# Z80Console0000.net
KiCad netlist of a schematic drawn in Altium Designer
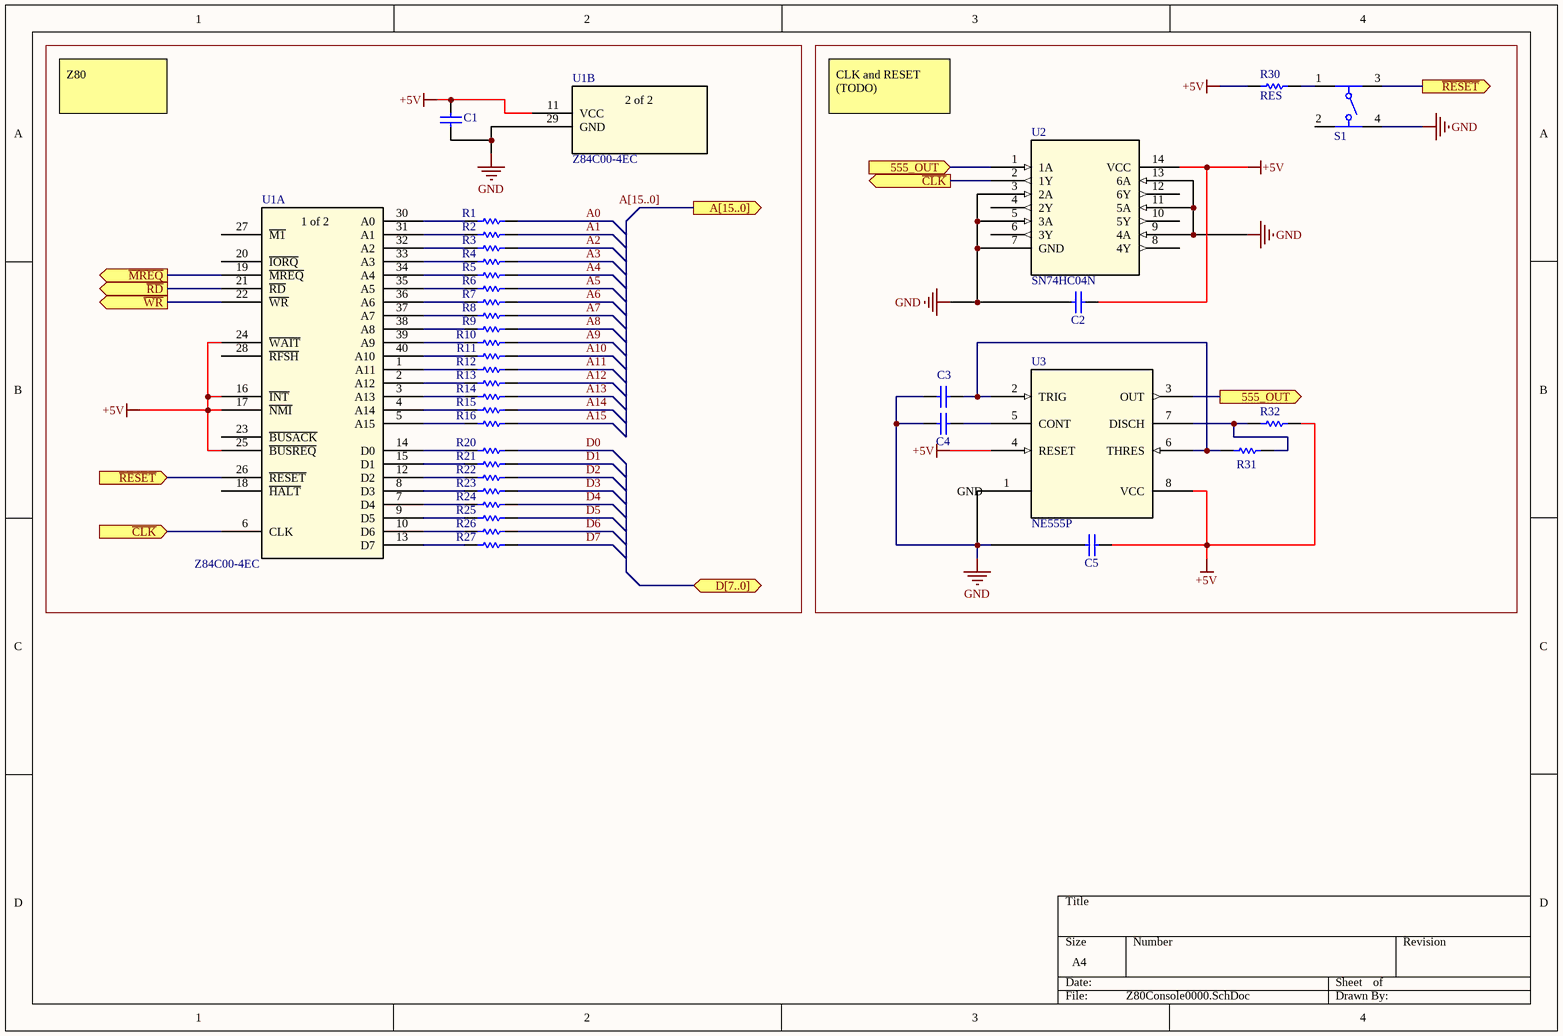
[diagram p0: Z80Console0000.SchDoc]

(export (version "E")
  (design (tool "Eeschema 10.0.6"))
  (components
    (comp (ref "C1")
      (value "CAP")
      (footprint "CAPC0603(1608)100_N")
      (libsource (lib "Passive SMD") (part "CAP"))
    )
    (comp (ref "C2")
      (value "CAP")
      (footprint "CAPC0603(1608)100_N")
      (libsource (lib "Passive SMD") (part "CAP"))
    )
    (comp (ref "C3")
      (value "CAP")
      (footprint "CAPC0603(1608)100_N")
      (libsource (lib "Passive SMD") (part "CAP"))
    )
    (comp (ref "C4")
      (value "CAP")
      (footprint "CAPC0603(1608)100_N")
      (libsource (lib "Passive SMD") (part "CAP"))
    )
    (comp (ref "C5")
      (value "CAP")
      (footprint "CAPC0603(1608)100_N")
      (libsource (lib "Passive SMD") (part "CAP"))
    )
    (comp (ref "R1") (value "RES") (footprint "RES_2512_MELF") (libsource (lib "Passive SMD") (part "RES")))
    (comp (ref "R2") (value "RES") (footprint "RES_2512_MELF") (libsource (lib "Passive SMD") (part "RES")))
    (comp (ref "R3") (value "RES") (footprint "RES_2512_MELF") (libsource (lib "Passive SMD") (part "RES")))
    (comp (ref "R4") (value "RES") (footprint "RES_2512_MELF") (libsource (lib "Passive SMD") (part "RES")))
    (comp (ref "R5") (value "RES") (footprint "RES_2512_MELF") (libsource (lib "Passive SMD") (part "RES")))
    (comp (ref "R6") (value "RES") (footprint "RES_2512_MELF") (libsource (lib "Passive SMD") (part "RES")))
    (comp (ref "R7") (value "RES") (footprint "RES_2512_MELF") (libsource (lib "Passive SMD") (part "RES")))
    (comp (ref "R8") (value "RES") (footprint "RES_2512_MELF") (libsource (lib "Passive SMD") (part "RES")))
    (comp (ref "R9") (value "RES") (footprint "RES_2512_MELF") (libsource (lib "Passive SMD") (part "RES")))
    (comp (ref "R10") (value "RES") (footprint "RES_2512_MELF") (libsource (lib "Passive SMD") (part "RES")))
    (comp (ref "R11") (value "RES") (footprint "RES_2512_MELF") (libsource (lib "Passive SMD") (part "RES")))
    (comp (ref "R12") (value "RES") (footprint "RES_2512_MELF") (libsource (lib "Passive SMD") (part "RES")))
    (comp (ref "R13") (value "RES") (footprint "RES_2512_MELF") (libsource (lib "Passive SMD") (part "RES")))
    (comp (ref "R14") (value "RES") (footprint "RES_2512_MELF") (libsource (lib "Passive SMD") (part "RES")))
    (comp (ref "R15") (value "RES") (footprint "RES_2512_MELF") (libsource (lib "Passive SMD") (part "RES")))
    (comp (ref "R16") (value "RES") (footprint "RES_2512_MELF") (libsource (lib "Passive SMD") (part "RES")))
    (comp (ref "R20") (value "RES") (footprint "RES_2512_MELF") (libsource (lib "Passive SMD") (part "RES")))
    (comp (ref "R21") (value "RES") (footprint "RES_2512_MELF") (libsource (lib "Passive SMD") (part "RES")))
    (comp (ref "R22") (value "RES") (footprint "RES_2512_MELF") (libsource (lib "Passive SMD") (part "RES")))
    (comp (ref "R23") (value "RES") (footprint "RES_2512_MELF") (libsource (lib "Passive SMD") (part "RES")))
    (comp (ref "R24") (value "RES") (footprint "RES_2512_MELF") (libsource (lib "Passive SMD") (part "RES")))
    (comp (ref "R25") (value "RES") (footprint "RES_2512_MELF") (libsource (lib "Passive SMD") (part "RES")))
    (comp (ref "R26") (value "RES") (footprint "RES_2512_MELF") (libsource (lib "Passive SMD") (part "RES")))
    (comp (ref "R27") (value "RES") (footprint "RES_2512_MELF") (libsource (lib "Passive SMD") (part "RES")))
    (comp (ref "R30") (value "RES") (footprint "RES_2512_MELF") (libsource (lib "Passive SMD") (part "RES")))
    (comp (ref "R31") (value "RES") (footprint "RES_2512_MELF") (libsource (lib "Passive SMD") (part "RES")))
    (comp (ref "R32") (value "RES") (footprint "RES_2512_MELF") (libsource (lib "Passive SMD") (part "RES")))
    (comp (ref "S1")
      (value "430156043726")
      (footprint "4301x60437x6_6x6x4.3")
      (description "WS-TATV 6x6mm Tact Switch, THT version")
      (fields (field (name "PUBLISHER") "Wurth Elektronik"))
      (libsource (lib "Wurth_WS-TATV-rev17a") (part "430156043726"))
    )
    (comp (ref "U1")
      (value "Z84C00-4EC")
      (footprint "DIP40_600_ZIL")
      (description "No Description Available")
      (fields (field (name "COPYRIGHT") "Copyright (C) 2025 Ultra Librarian. All rights reserved."))
      (libsource (lib "") (part "Z84C00-4EC_1"))
    )
    (comp (ref "U2")
      (value "SN74HC04N")
      (footprint "N14")
      (description "6-ch, 2-V to 6-V inverters 14-PDIP -40 to 85")
      (fields (field (name "COPYRIGHT") "Copyright (C) 2025 Ultra Librarian. All rights reserved."))
      (libsource (lib "Z80Console") (part "SN74HC04N"))
    )
    (comp (ref "U3")
      (value "NE555P")
      (footprint "P8")
      (description "Single Precision Timer 8-PDIP 0 to 70")
      (fields (field (name "COPYRIGHT") "Copyright (C) 2025 Ultra Librarian. All rights reserved."))
      (libsource (lib "Z80Console") (part "NE555P"))
    )
  )
  (nets
    (net (code "1") (name "+5V") (class "Default")
      (node (ref "C1") (pin "2") (pinfunction "2_2") (pintype "passive"))
      (node (ref "C2") (pin "1") (pinfunction "1_1") (pintype "passive"))
      (node (ref "C5") (pin "2") (pinfunction "2_2") (pintype "passive"))
      (node (ref "R30") (pin "2") (pinfunction "2_2") (pintype "passive"))
      (node (ref "R32") (pin "1") (pinfunction "1_1") (pintype "passive"))
      (node (ref "U1") (pin "11") (pinfunction "VCC_11") (pintype "passive"))
      (node (ref "U1") (pin "16") (pinfunction "INT_16") (pintype "passive"))
      (node (ref "U1") (pin "17") (pinfunction "NMI_17") (pintype "passive"))
      (node (ref "U1") (pin "24") (pinfunction "WAIT_24") (pintype "passive"))
      (node (ref "U1") (pin "25") (pinfunction "BUSREQ_25") (pintype "passive"))
      (node (ref "U2") (pin "14") (pinfunction "VCC_14") (pintype "power_in"))
      (node (ref "U3") (pin "4") (pinfunction "RESET_4") (pintype "input"))
      (node (ref "U3") (pin "8") (pinfunction "VCC_8") (pintype "power_in"))
    )
    (net (code "2") (name "/555_OUT") (class "Default")
      (node (ref "U2") (pin "1") (pinfunction "1A_1") (pintype "input"))
      (node (ref "U3") (pin "3") (pinfunction "OUT_3") (pintype "output"))
    )
    (net (code "3") (name "/A0") (class "Default")
      (node (ref "R1") (pin "1") (pinfunction "1_1") (pintype "passive"))
    )
    (net (code "4") (name "/A1") (class "Default")
      (node (ref "R2") (pin "1") (pinfunction "1_1") (pintype "passive"))
    )
    (net (code "5") (name "/A2") (class "Default")
      (node (ref "R3") (pin "1") (pinfunction "1_1") (pintype "passive"))
    )
    (net (code "6") (name "/A3") (class "Default")
      (node (ref "R4") (pin "1") (pinfunction "1_1") (pintype "passive"))
    )
    (net (code "7") (name "/A4") (class "Default")
      (node (ref "R5") (pin "1") (pinfunction "1_1") (pintype "passive"))
    )
    (net (code "8") (name "/A5") (class "Default")
      (node (ref "R6") (pin "1") (pinfunction "1_1") (pintype "passive"))
    )
    (net (code "9") (name "/A6") (class "Default")
      (node (ref "R7") (pin "1") (pinfunction "1_1") (pintype "passive"))
    )
    (net (code "10") (name "/A7") (class "Default")
      (node (ref "R8") (pin "1") (pinfunction "1_1") (pintype "passive"))
    )
    (net (code "11") (name "/A8") (class "Default")
      (node (ref "R9") (pin "1") (pinfunction "1_1") (pintype "passive"))
    )
    (net (code "12") (name "/A9") (class "Default")
      (node (ref "R10") (pin "1") (pinfunction "1_1") (pintype "passive"))
    )
    (net (code "13") (name "/A10") (class "Default")
      (node (ref "R11") (pin "1") (pinfunction "1_1") (pintype "passive"))
    )
    (net (code "14") (name "/A11") (class "Default")
      (node (ref "R12") (pin "1") (pinfunction "1_1") (pintype "passive"))
    )
    (net (code "15") (name "/A12") (class "Default")
      (node (ref "R13") (pin "1") (pinfunction "1_1") (pintype "passive"))
    )
    (net (code "16") (name "/A13") (class "Default")
      (node (ref "R14") (pin "1") (pinfunction "1_1") (pintype "passive"))
    )
    (net (code "17") (name "/A14") (class "Default")
      (node (ref "R15") (pin "1") (pinfunction "1_1") (pintype "passive"))
    )
    (net (code "18") (name "/A15") (class "Default")
      (node (ref "R16") (pin "1") (pinfunction "1_1") (pintype "passive"))
    )
    (net (code "20") (name "/CLK") (class "Default")
      (node (ref "U1") (pin "6") (pinfunction "CLK_6") (pintype "passive"))
      (node (ref "U2") (pin "2") (pinfunction "1Y_2") (pintype "output"))
    )
    (net (code "21") (name "/D0") (class "Default")
      (node (ref "R20") (pin "1") (pinfunction "1_1") (pintype "passive"))
    )
    (net (code "22") (name "/D1") (class "Default")
      (node (ref "R21") (pin "1") (pinfunction "1_1") (pintype "passive"))
    )
    (net (code "23") (name "/D2") (class "Default")
      (node (ref "R22") (pin "1") (pinfunction "1_1") (pintype "passive"))
    )
    (net (code "24") (name "/D3") (class "Default")
      (node (ref "R23") (pin "1") (pinfunction "1_1") (pintype "passive"))
    )
    (net (code "25") (name "/D4") (class "Default")
      (node (ref "R24") (pin "1") (pinfunction "1_1") (pintype "passive"))
    )
    (net (code "26") (name "/D5") (class "Default")
      (node (ref "R25") (pin "1") (pinfunction "1_1") (pintype "passive"))
    )
    (net (code "27") (name "/D6") (class "Default")
      (node (ref "R26") (pin "1") (pinfunction "1_1") (pintype "passive"))
    )
    (net (code "28") (name "/D7") (class "Default")
      (node (ref "R27") (pin "1") (pinfunction "1_1") (pintype "passive"))
    )
    (net (code "30") (name "/MREQ") (class "Default")
      (node (ref "U1") (pin "19") (pinfunction "MREQ_19") (pintype "passive"))
    )
    (net (code "31") (name "/RD") (class "Default")
      (node (ref "U1") (pin "21") (pinfunction "RD_21") (pintype "passive"))
    )
    (net (code "32") (name "/RESET") (class "Default")
      (node (ref "S1") (pin "3") (pinfunction "3_3") (pintype "passive"))
      (node (ref "U1") (pin "26") (pinfunction "RESET_26") (pintype "passive"))
    )
    (net (code "33") (name "/WR") (class "Default")
      (node (ref "U1") (pin "22") (pinfunction "WR_22") (pintype "passive"))
    )
    (net (code "34") (name "GND") (class "Default")
      (node (ref "C1") (pin "1") (pinfunction "1_1") (pintype "passive"))
      (node (ref "C2") (pin "2") (pinfunction "2_2") (pintype "passive"))
      (node (ref "C3") (pin "2") (pinfunction "2_2") (pintype "passive"))
      (node (ref "C4") (pin "2") (pinfunction "2_2") (pintype "passive"))
      (node (ref "C5") (pin "1") (pinfunction "1_1") (pintype "passive"))
      (node (ref "S1") (pin "4") (pinfunction "4_4") (pintype "passive"))
      (node (ref "U1") (pin "29") (pinfunction "GND_29") (pintype "passive"))
      (node (ref "U2") (pin "11") (pinfunction "5A_11") (pintype "input"))
      (node (ref "U2") (pin "13") (pinfunction "6A_13") (pintype "input"))
      (node (ref "U2") (pin "3") (pinfunction "2A_3") (pintype "input"))
      (node (ref "U2") (pin "5") (pinfunction "3A_5") (pintype "input"))
      (node (ref "U2") (pin "7") (pinfunction "GND_7") (pintype "power_in"))
      (node (ref "U2") (pin "9") (pinfunction "4A_9") (pintype "input"))
    )
    (net (code "35") (name "Net-(R30-Pad1)") (class "Default")
      (node (ref "R30") (pin "1") (pinfunction "1_1") (pintype "passive"))
      (node (ref "S1") (pin "1") (pinfunction "1_1") (pintype "passive"))
    )
    (net (code "36") (name "Net-(U1A-A0)") (class "Default")
      (node (ref "R1") (pin "2") (pinfunction "2_2") (pintype "passive"))
      (node (ref "U1") (pin "30") (pinfunction "A0_30") (pintype "passive"))
    )
    (net (code "37") (name "Net-(U1A-A1)") (class "Default")
      (node (ref "R2") (pin "2") (pinfunction "2_2") (pintype "passive"))
      (node (ref "U1") (pin "31") (pinfunction "A1_31") (pintype "passive"))
    )
    (net (code "38") (name "Net-(U1A-A2)") (class "Default")
      (node (ref "R3") (pin "2") (pinfunction "2_2") (pintype "passive"))
      (node (ref "U1") (pin "32") (pinfunction "A2_32") (pintype "passive"))
    )
    (net (code "39") (name "Net-(U1A-A3)") (class "Default")
      (node (ref "R4") (pin "2") (pinfunction "2_2") (pintype "passive"))
      (node (ref "U1") (pin "33") (pinfunction "A3_33") (pintype "passive"))
    )
    (net (code "40") (name "Net-(U1A-A4)") (class "Default")
      (node (ref "R5") (pin "2") (pinfunction "2_2") (pintype "passive"))
      (node (ref "U1") (pin "34") (pinfunction "A4_34") (pintype "passive"))
    )
    (net (code "41") (name "Net-(U1A-A5)") (class "Default")
      (node (ref "R6") (pin "2") (pinfunction "2_2") (pintype "passive"))
      (node (ref "U1") (pin "35") (pinfunction "A5_35") (pintype "passive"))
    )
    (net (code "42") (name "Net-(U1A-A6)") (class "Default")
      (node (ref "R7") (pin "2") (pinfunction "2_2") (pintype "passive"))
      (node (ref "U1") (pin "36") (pinfunction "A6_36") (pintype "passive"))
    )
    (net (code "43") (name "Net-(U1A-A7)") (class "Default")
      (node (ref "R8") (pin "2") (pinfunction "2_2") (pintype "passive"))
      (node (ref "U1") (pin "37") (pinfunction "A7_37") (pintype "passive"))
    )
    (net (code "44") (name "Net-(U1A-A8)") (class "Default")
      (node (ref "R9") (pin "2") (pinfunction "2_2") (pintype "passive"))
      (node (ref "U1") (pin "38") (pinfunction "A8_38") (pintype "passive"))
    )
    (net (code "45") (name "Net-(U1A-A9)") (class "Default")
      (node (ref "R10") (pin "2") (pinfunction "2_2") (pintype "passive"))
      (node (ref "U1") (pin "39") (pinfunction "A9_39") (pintype "passive"))
    )
    (net (code "46") (name "Net-(U1A-A10)") (class "Default")
      (node (ref "R11") (pin "2") (pinfunction "2_2") (pintype "passive"))
      (node (ref "U1") (pin "40") (pinfunction "A10_40") (pintype "passive"))
    )
    (net (code "47") (name "Net-(U1A-A11)") (class "Default")
      (node (ref "R12") (pin "2") (pinfunction "2_2") (pintype "passive"))
      (node (ref "U1") (pin "1") (pinfunction "A11_1") (pintype "passive"))
    )
    (net (code "48") (name "Net-(U1A-A12)") (class "Default")
      (node (ref "R13") (pin "2") (pinfunction "2_2") (pintype "passive"))
      (node (ref "U1") (pin "2") (pinfunction "A12_2") (pintype "passive"))
    )
    (net (code "49") (name "Net-(U1A-A13)") (class "Default")
      (node (ref "R14") (pin "2") (pinfunction "2_2") (pintype "passive"))
      (node (ref "U1") (pin "3") (pinfunction "A13_3") (pintype "passive"))
    )
    (net (code "50") (name "Net-(U1A-A14)") (class "Default")
      (node (ref "R15") (pin "2") (pinfunction "2_2") (pintype "passive"))
      (node (ref "U1") (pin "4") (pinfunction "A14_4") (pintype "passive"))
    )
    (net (code "51") (name "Net-(U1A-A15)") (class "Default")
      (node (ref "R16") (pin "2") (pinfunction "2_2") (pintype "passive"))
      (node (ref "U1") (pin "5") (pinfunction "A15_5") (pintype "passive"))
    )
    (net (code "52") (name "Net-(U1A-D0)") (class "Default")
      (node (ref "R20") (pin "2") (pinfunction "2_2") (pintype "passive"))
      (node (ref "U1") (pin "14") (pinfunction "D0_14") (pintype "passive"))
    )
    (net (code "53") (name "Net-(U1A-D1)") (class "Default")
      (node (ref "R21") (pin "2") (pinfunction "2_2") (pintype "passive"))
      (node (ref "U1") (pin "15") (pinfunction "D1_15") (pintype "passive"))
    )
    (net (code "54") (name "Net-(U1A-D2)") (class "Default")
      (node (ref "R22") (pin "2") (pinfunction "2_2") (pintype "passive"))
      (node (ref "U1") (pin "12") (pinfunction "D2_12") (pintype "passive"))
    )
    (net (code "55") (name "Net-(U1A-D3)") (class "Default")
      (node (ref "R23") (pin "2") (pinfunction "2_2") (pintype "passive"))
      (node (ref "U1") (pin "8") (pinfunction "D3_8") (pintype "passive"))
    )
    (net (code "56") (name "Net-(U1A-D4)") (class "Default")
      (node (ref "R24") (pin "2") (pinfunction "2_2") (pintype "passive"))
      (node (ref "U1") (pin "7") (pinfunction "D4_7") (pintype "passive"))
    )
    (net (code "57") (name "Net-(U1A-D5)") (class "Default")
      (node (ref "R25") (pin "2") (pinfunction "2_2") (pintype "passive"))
      (node (ref "U1") (pin "9") (pinfunction "D5_9") (pintype "passive"))
    )
    (net (code "58") (name "Net-(U1A-D6)") (class "Default")
      (node (ref "R26") (pin "2") (pinfunction "2_2") (pintype "passive"))
      (node (ref "U1") (pin "10") (pinfunction "D6_10") (pintype "passive"))
    )
    (net (code "59") (name "Net-(U1A-D7)") (class "Default")
      (node (ref "R27") (pin "2") (pinfunction "2_2") (pintype "passive"))
      (node (ref "U1") (pin "13") (pinfunction "D7_13") (pintype "passive"))
    )
    (net (code "60") (name "Net-(U3-CONT)") (class "Default")
      (node (ref "C4") (pin "1") (pinfunction "1_1") (pintype "passive"))
      (node (ref "U3") (pin "5") (pinfunction "CONT_5") (pintype "passive"))
    )
    (net (code "61") (name "Net-(U3-DISCH)") (class "Default")
      (node (ref "R31") (pin "1") (pinfunction "1_1") (pintype "passive"))
      (node (ref "R32") (pin "2") (pinfunction "2_2") (pintype "passive"))
      (node (ref "U3") (pin "7") (pinfunction "DISCH_7") (pintype "passive"))
    )
    (net (code "62") (name "Net-(U3-THRES)") (class "Default")
      (node (ref "C3") (pin "1") (pinfunction "1_1") (pintype "passive"))
      (node (ref "R31") (pin "2") (pinfunction "2_2") (pintype "passive"))
      (node (ref "U3") (pin "2") (pinfunction "TRIG_2") (pintype "input"))
      (node (ref "U3") (pin "6") (pinfunction "THRES_6") (pintype "input"))
    )
    (net (code "63") (name "unconnected-(S1-Pad2)") (class "Default")
      (node (ref "S1") (pin "2") (pinfunction "2_2") (pintype "passive"))
    )
    (net (code "64") (name "unconnected-(U1A-BUSACK-Pad23)") (class "Default")
      (node (ref "U1") (pin "23") (pinfunction "BUSACK_23") (pintype "passive"))
    )
    (net (code "65") (name "unconnected-(U1A-HALT-Pad18)") (class "Default")
      (node (ref "U1") (pin "18") (pinfunction "HALT_18") (pintype "passive"))
    )
    (net (code "66") (name "unconnected-(U1A-IORQ-Pad20)") (class "Default")
      (node (ref "U1") (pin "20") (pinfunction "IORQ_20") (pintype "passive"))
    )
    (net (code "67") (name "unconnected-(U1A-M1-Pad27)") (class "Default")
      (node (ref "U1") (pin "27") (pinfunction "M1_27") (pintype "passive"))
    )
    (net (code "68") (name "unconnected-(U1A-RFSH-Pad28)") (class "Default")
      (node (ref "U1") (pin "28") (pinfunction "RFSH_28") (pintype "passive"))
    )
    (net (code "69") (name "unconnected-(U2-2Y-Pad4)") (class "Default")
      (node (ref "U2") (pin "4") (pinfunction "2Y_4") (pintype "output"))
    )
    (net (code "70") (name "unconnected-(U2-3Y-Pad6)") (class "Default")
      (node (ref "U2") (pin "6") (pinfunction "3Y_6") (pintype "output"))
    )
    (net (code "71") (name "unconnected-(U2-4Y-Pad8)") (class "Default")
      (node (ref "U2") (pin "8") (pinfunction "4Y_8") (pintype "output"))
    )
    (net (code "72") (name "unconnected-(U2-5Y-Pad10)") (class "Default")
      (node (ref "U2") (pin "10") (pinfunction "5Y_10") (pintype "output"))
    )
    (net (code "73") (name "unconnected-(U2-6Y-Pad12)") (class "Default")
      (node (ref "U2") (pin "12") (pinfunction "6Y_12") (pintype "output"))
    )
    (net (code "74") (name "unconnected-(U3-GND-Pad1)") (class "Default")
      (node (ref "U3") (pin "1") (pinfunction "GND_1") (pintype "power_in"))
    )
  )
)
